# POWER.net
KiCad netlist of a schematic drawn in Altium Designer
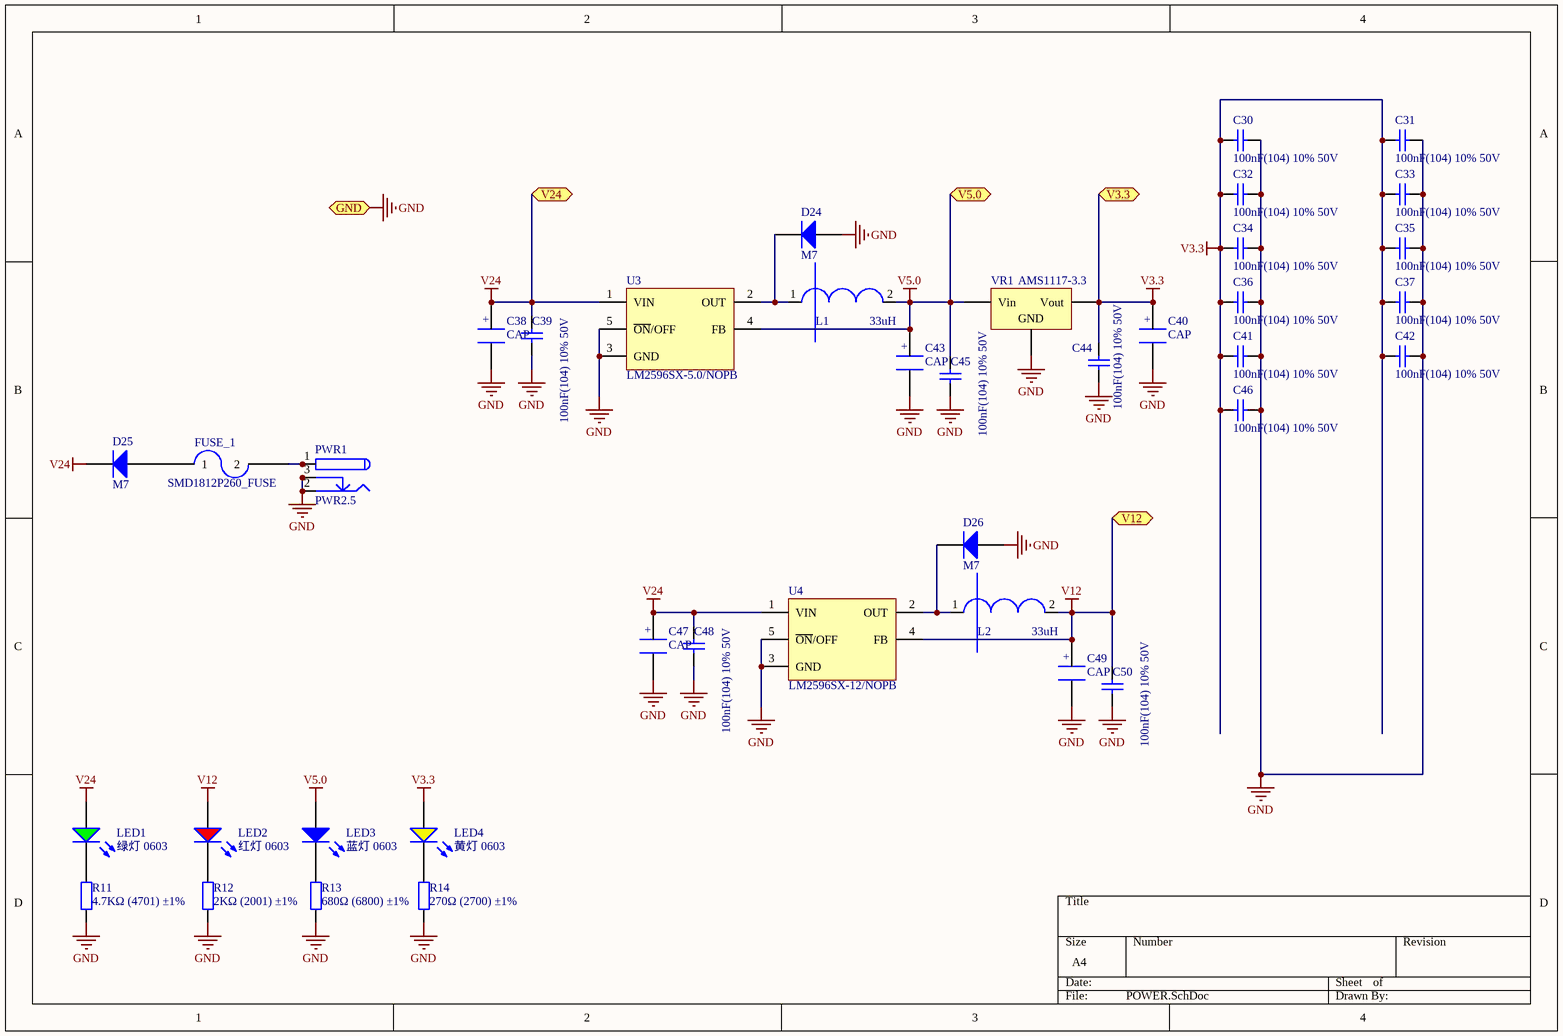
[diagram p0: POWER.SchDoc]

(export (version "E")
  (design (tool "Eeschema 10.0.6"))
  (components
    (comp (ref "C30")
      (value "100nF(104) 10% 50V")
      (footprint "0805_C")
      (description "贴片电容")
      (libsource (lib "Miscellaneous Devices LC") (part "0805 100nF(104) 10% 50V"))
    )
    (comp (ref "C31")
      (value "100nF(104) 10% 50V")
      (footprint "0805_C")
      (description "贴片电容")
      (libsource (lib "Miscellaneous Devices LC") (part "0805 100nF(104) 10% 50V"))
    )
    (comp (ref "C32")
      (value "100nF(104) 10% 50V")
      (footprint "0805_C")
      (description "贴片电容")
      (libsource (lib "Miscellaneous Devices LC") (part "0805 100nF(104) 10% 50V"))
    )
    (comp (ref "C33")
      (value "100nF(104) 10% 50V")
      (footprint "0805_C")
      (description "贴片电容")
      (libsource (lib "Miscellaneous Devices LC") (part "0805 100nF(104) 10% 50V"))
    )
    (comp (ref "C34")
      (value "100nF(104) 10% 50V")
      (footprint "0805_C")
      (description "贴片电容")
      (libsource (lib "Miscellaneous Devices LC") (part "0805 100nF(104) 10% 50V"))
    )
    (comp (ref "C35")
      (value "100nF(104) 10% 50V")
      (footprint "0805_C")
      (description "贴片电容")
      (libsource (lib "Miscellaneous Devices LC") (part "0805 100nF(104) 10% 50V"))
    )
    (comp (ref "C36")
      (value "100nF(104) 10% 50V")
      (footprint "0805_C")
      (description "贴片电容")
      (libsource (lib "Miscellaneous Devices LC") (part "0805 100nF(104) 10% 50V"))
    )
    (comp (ref "C37")
      (value "100nF(104) 10% 50V")
      (footprint "0805_C")
      (description "贴片电容")
      (libsource (lib "Miscellaneous Devices LC") (part "0805 100nF(104) 10% 50V"))
    )
    (comp (ref "C38") (value "CAP") (footprint "8X12_CAP") (libsource (lib "mylib") (part "CAP")))
    (comp (ref "C39")
      (value "100nF(104) 10% 50V")
      (footprint "0805_C")
      (description "贴片电容")
      (libsource (lib "Miscellaneous Devices LC") (part "0805 100nF(104) 10% 50V"))
    )
    (comp (ref "C40") (value "CAP") (footprint "8X12_CAP") (libsource (lib "mylib") (part "CAP")))
    (comp (ref "C41")
      (value "100nF(104) 10% 50V")
      (footprint "0805_C")
      (description "贴片电容")
      (libsource (lib "Miscellaneous Devices LC") (part "0805 100nF(104) 10% 50V"))
    )
    (comp (ref "C42")
      (value "100nF(104) 10% 50V")
      (footprint "0805_C")
      (description "贴片电容")
      (libsource (lib "Miscellaneous Devices LC") (part "0805 100nF(104) 10% 50V"))
    )
    (comp (ref "C43") (value "CAP") (footprint "8X12_CAP") (libsource (lib "mylib") (part "CAP")))
    (comp (ref "C44")
      (value "100nF(104) 10% 50V")
      (footprint "0805_C")
      (description "贴片电容")
      (libsource (lib "Miscellaneous Devices LC") (part "0805 100nF(104) 10% 50V"))
    )
    (comp (ref "C45")
      (value "100nF(104) 10% 50V")
      (footprint "0805_C")
      (description "贴片电容")
      (libsource (lib "Miscellaneous Devices LC") (part "0805 100nF(104) 10% 50V"))
    )
    (comp (ref "C46")
      (value "100nF(104) 10% 50V")
      (footprint "0805_C")
      (description "贴片电容")
      (libsource (lib "Miscellaneous Devices LC") (part "0805 100nF(104) 10% 50V"))
    )
    (comp (ref "C47") (value "CAP") (footprint "8X12_CAP") (libsource (lib "mylib") (part "CAP")))
    (comp (ref "C48")
      (value "100nF(104) 10% 50V")
      (footprint "0805_C")
      (description "贴片电容")
      (libsource (lib "Miscellaneous Devices LC") (part "0805 100nF(104) 10% 50V"))
    )
    (comp (ref "C49") (value "CAP") (footprint "8X12_CAP") (libsource (lib "mylib") (part "CAP")))
    (comp (ref "C50")
      (value "100nF(104) 10% 50V")
      (footprint "0805_C")
      (description "贴片电容")
      (libsource (lib "Miscellaneous Devices LC") (part "0805 100nF(104) 10% 50V"))
    )
    (comp (ref "D24")
      (value "M7")
      (footprint "SMA(DO-214AC)_S1")
      (description "二极管")
      (libsource (lib "Miscellaneous Devices LC") (part "SMA(DO-214AC) M7"))
    )
    (comp (ref "D25")
      (value "M7")
      (footprint "SMA(DO-214AC)_S1")
      (description "二极管")
      (libsource (lib "Miscellaneous Devices LC") (part "SMA(DO-214AC) M7"))
    )
    (comp (ref "D26")
      (value "M7")
      (footprint "SMA(DO-214AC)_S1")
      (description "二极管")
      (libsource (lib "Miscellaneous Devices LC") (part "SMA(DO-214AC) M7"))
    )
    (comp (ref "FUSE_1")
      (value "SMD1812P260_FUSE")
      (footprint "SMD1812P260")
      (libsource (lib "mylib") (part "SMD1812P260_FUSE"))
    )
    (comp (ref "L1") (value "33uH") (footprint "L_127") (libsource (lib "mylib") (part "33uH")))
    (comp (ref "L2") (value "33uH") (footprint "L_127") (libsource (lib "mylib") (part "33uH")))
    (comp (ref "LED1")
      (value "绿灯 0603")
      (footprint "0603_LED_S1")
      (description "发光二极管")
      (libsource (lib "Miscellaneous Devices LC") (part "0603 绿灯"))
    )
    (comp (ref "LED2")
      (value "红灯 0603")
      (footprint "0603_LED_S1")
      (description "发光二极管")
      (libsource (lib "Miscellaneous Devices LC") (part "0603 红灯"))
    )
    (comp (ref "LED3")
      (value "蓝灯 0603")
      (footprint "0603_LED_S1")
      (description "发光二极管")
      (libsource (lib "Miscellaneous Devices LC") (part "0603 蓝灯"))
    )
    (comp (ref "LED4")
      (value "黄灯 0603")
      (footprint "0603_LED_S1")
      (description "发光二极管")
      (libsource (lib "Miscellaneous Devices LC") (part "0603 黄灯"))
    )
    (comp (ref "PWR1")
      (value "PWR2.5")
      (footprint "KLD-0202")
      (description "Low Voltage Power Supply Connector")
      (fields (field (name "PUBLISHER") "Altium Limited"))
      (libsource (lib "Miscellaneous Connectors") (part "PWR2.5"))
    )
    (comp (ref "R11")
      (value "4.7KΩ (4701) ±1%")
      (footprint "0805_R")
      (description "贴片电阻")
      (libsource (lib "Miscellaneous Devices LC") (part "0805 4.7KΩ (4701) 1%"))
    )
    (comp (ref "R12")
      (value "2KΩ (2001) ±1%")
      (footprint "0805_R")
      (description "贴片电阻")
      (libsource (lib "Miscellaneous Devices LC") (part "0805 2KΩ (2001) 1%"))
    )
    (comp (ref "R13")
      (value "680Ω (6800) ±1%")
      (footprint "0805_R")
      (description "贴片电阻")
      (libsource (lib "Miscellaneous Devices LC") (part "0805 680Ω (6800) 1%"))
    )
    (comp (ref "R14")
      (value "270Ω (2700) ±1%")
      (footprint "0805_R")
      (description "贴片电阻")
      (libsource (lib "Miscellaneous Devices LC") (part "0805 270Ω (2700) 1%"))
    )
    (comp (ref "U3")
      (value "LM2596SX-5.0/NOPB")
      (footprint "TO-263-5")
      (description "DC-DC芯片")
      (libsource (lib "Miscellaneous Devices LC") (part "LM2596SX-5.0/NOPB_[C10002]"))
    )
    (comp (ref "U4")
      (value "LM2596SX-12/NOPB")
      (footprint "TO-263-5")
      (description "DC-DC芯片")
      (libsource (lib "Miscellaneous Devices LC") (part "LM2596SX-5.0/NOPB_[C10002]"))
    )
    (comp (ref "VR1")
      (value "AMS1117-3.3")
      (footprint "SOT-223")
      (description "低压差线性稳压(LDO)")
      (libsource (lib "Miscellaneous Devices LC") (part "SOT-223 AMS1117-3.3"))
    )
  )
  (nets
    (net (code "1") (name "GND") (class "Default")
      (node (ref "C30") (pin "1") (pinfunction "1_1") (pintype "passive"))
      (node (ref "C31") (pin "1") (pinfunction "1_1") (pintype "passive"))
      (node (ref "C32") (pin "1") (pinfunction "1_1") (pintype "passive"))
      (node (ref "C33") (pin "1") (pinfunction "1_1") (pintype "passive"))
      (node (ref "C34") (pin "1") (pinfunction "1_1") (pintype "passive"))
      (node (ref "C35") (pin "1") (pinfunction "1_1") (pintype "passive"))
      (node (ref "C36") (pin "1") (pinfunction "1_1") (pintype "passive"))
      (node (ref "C37") (pin "1") (pinfunction "1_1") (pintype "passive"))
      (node (ref "C38") (pin "2") (pinfunction "2_2") (pintype "passive"))
      (node (ref "C39") (pin "2") (pinfunction "2_2") (pintype "passive"))
      (node (ref "C40") (pin "2") (pinfunction "2_2") (pintype "passive"))
      (node (ref "C41") (pin "1") (pinfunction "1_1") (pintype "passive"))
      (node (ref "C42") (pin "1") (pinfunction "1_1") (pintype "passive"))
      (node (ref "C43") (pin "2") (pinfunction "2_2") (pintype "passive"))
      (node (ref "C44") (pin "2") (pinfunction "2_2") (pintype "passive"))
      (node (ref "C45") (pin "2") (pinfunction "2_2") (pintype "passive"))
      (node (ref "C46") (pin "1") (pinfunction "1_1") (pintype "passive"))
      (node (ref "C47") (pin "2") (pinfunction "2_2") (pintype "passive"))
      (node (ref "C48") (pin "2") (pinfunction "2_2") (pintype "passive"))
      (node (ref "C49") (pin "2") (pinfunction "2_2") (pintype "passive"))
      (node (ref "C50") (pin "2") (pinfunction "2_2") (pintype "passive"))
      (node (ref "D24") (pin "1") (pinfunction "A_1") (pintype "passive"))
      (node (ref "D26") (pin "1") (pinfunction "A_1") (pintype "passive"))
      (node (ref "PWR1") (pin "2") (pinfunction "2_2") (pintype "power_in"))
      (node (ref "PWR1") (pin "2A") (pinfunction "2A_2A") (pintype "power_in"))
      (node (ref "PWR1") (pin "2B") (pinfunction "2B_2B") (pintype "power_in"))
      (node (ref "PWR1") (pin "3") (pinfunction "3_3") (pintype "power_in"))
      (node (ref "PWR1") (pin "3A") (pinfunction "3A_3A") (pintype "power_in"))
      (node (ref "PWR1") (pin "3B") (pinfunction "3B_3B") (pintype "power_in"))
      (node (ref "R11") (pin "1") (pinfunction "1_1") (pintype "passive"))
      (node (ref "R12") (pin "1") (pinfunction "1_1") (pintype "passive"))
      (node (ref "R13") (pin "1") (pinfunction "1_1") (pintype "passive"))
      (node (ref "R14") (pin "1") (pinfunction "1_1") (pintype "passive"))
      (node (ref "U3") (pin "3") (pinfunction "GND_3") (pintype "power_in"))
      (node (ref "U3") (pin "5") (pinfunction "~{ON}/OFF_5") (pintype "passive"))
      (node (ref "U4") (pin "3") (pinfunction "GND_3") (pintype "power_in"))
      (node (ref "U4") (pin "5") (pinfunction "~{ON}/OFF_5") (pintype "passive"))
      (node (ref "VR1") (pin "1") (pinfunction "GND_1") (pintype "passive"))
    )
    (net (code "2") (name "Net-(D24-K)") (class "Default")
      (node (ref "D24") (pin "2") (pinfunction "K_2") (pintype "passive"))
      (node (ref "L1") (pin "1") (pinfunction "1_1") (pintype "passive"))
      (node (ref "U3") (pin "2") (pinfunction "OUT_2") (pintype "power_in"))
    )
    (net (code "3") (name "Net-(D25-A)") (class "Default")
      (node (ref "D25") (pin "1") (pinfunction "A_1") (pintype "passive"))
      (node (ref "FUSE_1") (pin "1") (pinfunction "1_1") (pintype "passive"))
    )
    (net (code "4") (name "Net-(D26-K)") (class "Default")
      (node (ref "D26") (pin "2") (pinfunction "K_2") (pintype "passive"))
      (node (ref "L2") (pin "1") (pinfunction "1_1") (pintype "passive"))
      (node (ref "U4") (pin "2") (pinfunction "OUT_2") (pintype "power_in"))
    )
    (net (code "5") (name "Net-(FUSE_1-Pad2)") (class "Default")
      (node (ref "FUSE_1") (pin "2") (pinfunction "2_2") (pintype "passive"))
      (node (ref "PWR1") (pin "1") (pinfunction "1_1") (pintype "power_in"))
      (node (ref "PWR1") (pin "1A") (pinfunction "1A_1A") (pintype "power_in"))
      (node (ref "PWR1") (pin "1B") (pinfunction "1B_1B") (pintype "power_in"))
    )
    (net (code "6") (name "Net-(LED1-PadK)") (class "Default")
      (node (ref "LED1") (pin "K") (pinfunction "K_K") (pintype "passive"))
      (node (ref "R11") (pin "2") (pinfunction "2_2") (pintype "passive"))
    )
    (net (code "7") (name "Net-(LED2-PadK)") (class "Default")
      (node (ref "LED2") (pin "K") (pinfunction "K_K") (pintype "passive"))
      (node (ref "R12") (pin "2") (pinfunction "2_2") (pintype "passive"))
    )
    (net (code "8") (name "Net-(LED3-PadK)") (class "Default")
      (node (ref "LED3") (pin "K") (pinfunction "K_K") (pintype "passive"))
      (node (ref "R13") (pin "2") (pinfunction "2_2") (pintype "passive"))
    )
    (net (code "9") (name "Net-(LED4-PadK)") (class "Default")
      (node (ref "LED4") (pin "K") (pinfunction "K_K") (pintype "passive"))
      (node (ref "R14") (pin "2") (pinfunction "2_2") (pintype "passive"))
    )
    (net (code "10") (name "V3.3") (class "Default")
      (node (ref "C30") (pin "2") (pinfunction "2_2") (pintype "passive"))
      (node (ref "C31") (pin "2") (pinfunction "2_2") (pintype "passive"))
      (node (ref "C32") (pin "2") (pinfunction "2_2") (pintype "passive"))
      (node (ref "C33") (pin "2") (pinfunction "2_2") (pintype "passive"))
      (node (ref "C34") (pin "2") (pinfunction "2_2") (pintype "passive"))
      (node (ref "C35") (pin "2") (pinfunction "2_2") (pintype "passive"))
      (node (ref "C36") (pin "2") (pinfunction "2_2") (pintype "passive"))
      (node (ref "C37") (pin "2") (pinfunction "2_2") (pintype "passive"))
      (node (ref "C40") (pin "1") (pinfunction "1_1") (pintype "passive"))
      (node (ref "C41") (pin "2") (pinfunction "2_2") (pintype "passive"))
      (node (ref "C42") (pin "2") (pinfunction "2_2") (pintype "passive"))
      (node (ref "C44") (pin "1") (pinfunction "1_1") (pintype "passive"))
      (node (ref "C46") (pin "2") (pinfunction "2_2") (pintype "passive"))
      (node (ref "LED4") (pin "A") (pinfunction "A_A") (pintype "passive"))
      (node (ref "VR1") (pin "2") (pinfunction "Vout_2") (pintype "passive"))
    )
    (net (code "11") (name "V5.0") (class "Default")
      (node (ref "C43") (pin "1") (pinfunction "1_1") (pintype "passive"))
      (node (ref "C45") (pin "1") (pinfunction "1_1") (pintype "passive"))
      (node (ref "L1") (pin "2") (pinfunction "2_2") (pintype "passive"))
      (node (ref "LED3") (pin "A") (pinfunction "A_A") (pintype "passive"))
      (node (ref "U3") (pin "4") (pinfunction "FB_4") (pintype "passive"))
      (node (ref "VR1") (pin "3") (pinfunction "Vin_3") (pintype "passive"))
    )
    (net (code "12") (name "V12") (class "Default")
      (node (ref "C49") (pin "1") (pinfunction "1_1") (pintype "passive"))
      (node (ref "C50") (pin "1") (pinfunction "1_1") (pintype "passive"))
      (node (ref "L2") (pin "2") (pinfunction "2_2") (pintype "passive"))
      (node (ref "LED2") (pin "A") (pinfunction "A_A") (pintype "passive"))
      (node (ref "U4") (pin "4") (pinfunction "FB_4") (pintype "passive"))
    )
    (net (code "13") (name "V24") (class "Default")
      (node (ref "C38") (pin "1") (pinfunction "1_1") (pintype "passive"))
      (node (ref "C39") (pin "1") (pinfunction "1_1") (pintype "passive"))
      (node (ref "C47") (pin "1") (pinfunction "1_1") (pintype "passive"))
      (node (ref "C48") (pin "1") (pinfunction "1_1") (pintype "passive"))
      (node (ref "D25") (pin "2") (pinfunction "K_2") (pintype "passive"))
      (node (ref "LED1") (pin "A") (pinfunction "A_A") (pintype "passive"))
      (node (ref "U3") (pin "1") (pinfunction "VIN_1") (pintype "power_in"))
      (node (ref "U4") (pin "1") (pinfunction "VIN_1") (pintype "power_in"))
    )
  )
)
